# Power_Board_Schematic_Ver_A.net
KiCad netlist of a schematic drawn in Altium Designer
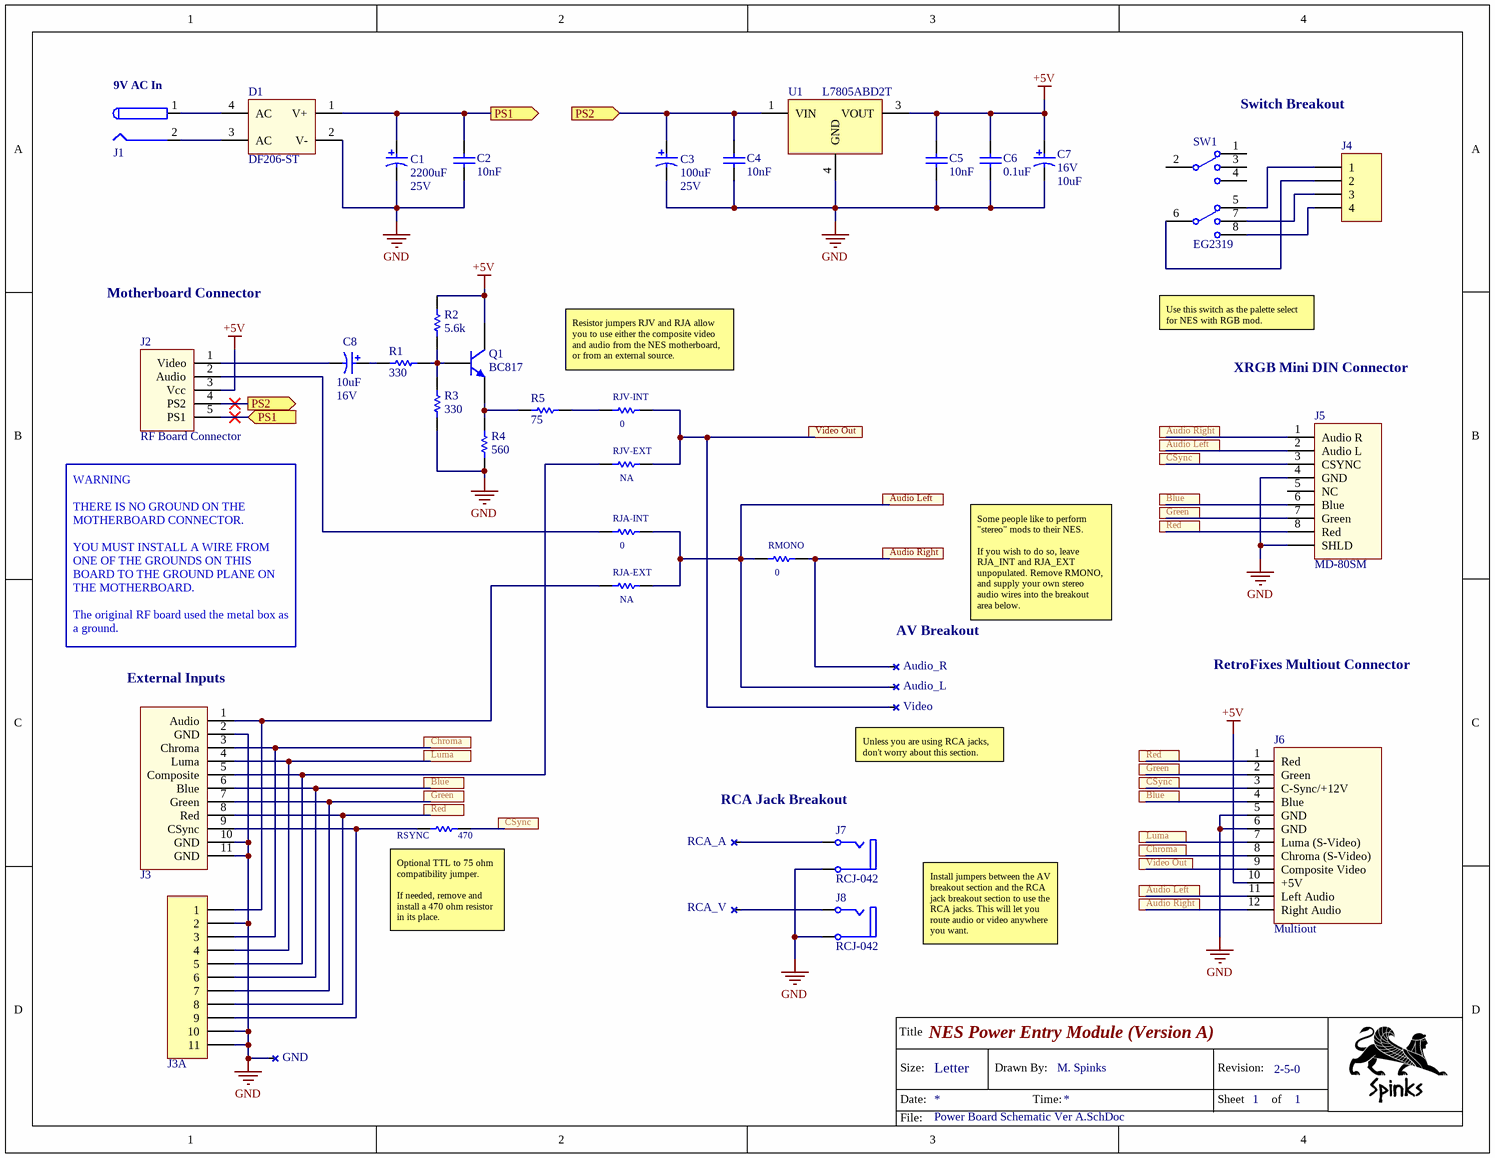
[diagram p0: Power Board Schematic Ver A.SchDoc]

(export (version "E")
  (design (tool "Eeschema 10.0.6"))
  (components
    (comp (ref "Audio_L")
      (value "Wire Pad")
      (footprint "WIREPAD-09-15")
      (description "Wire Pad, 1 Pin, Through Hole, Vertical")
      (libsource (lib "Connectors") (part "-Wire Pad"))
    )
    (comp (ref "Audio_R")
      (value "Wire Pad")
      (footprint "WIREPAD-09-15")
      (description "Wire Pad, 1 Pin, Through Hole, Vertical")
      (libsource (lib "Connectors") (part "-Wire Pad"))
    )
    (comp (ref "C1")
      (value "2200uF")
      (footprint "TH CAP-12.5X25MM-A1K2")
      (description "CAP, ALUM, TH, 12.5x25mm, 2200uF, 25V, 20%, Pitch 5.0mm")
      (fields
        (field (name "VOLTAGE") "25V")
        (field (name "REFERENCEPART") "ECA-1EHG222")
        (field (name "Comment") "Cap Aluminum")
      )
      (libsource (lib "Passive Components") (part "TH-ALUM-8-22-25V (ECA-1EHG222)"))
    )
    (comp (ref "C2")
      (value "10nF")
      (footprint "CAP 0805_N")
      (description "CAP, CER, 0805, 10nF, 50V, X7R, 10%")
      (fields (field (name "VOLTAGE") "50V") (field (name "REFERENCEPART") "VJ0603Y103KXACW1BC"))
      (libsource (lib "Passive Components") (part "0603-X7R-3-10-50V"))
    )
    (comp (ref "C3")
      (value "100uF")
      (footprint "TH CAP-6.3X11MM-A1K2")
      (description "CAP, ALUM, TH, 6.3x11mm, 100uF, 25V, 20%, Pitch 2.5mm")
      (fields
        (field (name "VOLTAGE") "25V")
        (field (name "REFERENCEPART") "ECA-1EM101")
        (field (name "Comment") "Cap Aluminum")
      )
      (libsource (lib "Passive Components") (part "TH-ALUM-7-10-25V (ECA-1EM101)"))
    )
    (comp (ref "C4")
      (value "10nF")
      (footprint "CAP 0805_N")
      (description "CAP, CER, 0805, 10nF, 50V, X7R, 10%")
      (fields (field (name "VOLTAGE") "50V") (field (name "REFERENCEPART") "VJ0603Y103KXACW1BC"))
      (libsource (lib "Passive Components") (part "0603-X7R-3-10-50V"))
    )
    (comp (ref "C5")
      (value "10nF")
      (footprint "CAP 0805_N")
      (description "CAP, CER, 0805, 10nF, 50V, X7R, 10%")
      (fields (field (name "VOLTAGE") "50V") (field (name "REFERENCEPART") "VJ0603Y103KXACW1BC"))
      (libsource (lib "Passive Components") (part "0603-X7R-3-10-50V"))
    )
    (comp (ref "C6")
      (value "0.1uF")
      (footprint "CAP 0805_N")
      (description "CAP, CER, 0805, 0.1uF, 50V, X7R, 10%")
      (fields (field (name "VOLTAGE") "50V") (field (name "REFERENCEPART") "VJ0805Y104KXXCW1BC"))
      (libsource (lib "Passive Components") (part "0805-X7R-4-10-50V"))
    )
    (comp (ref "C7")
      (value "10uF")
      (footprint "CAP EIA-A (3216) A1K2")
      (description "CAP, TANT,  1206, 10uF, 16V, 10%")
      (fields (field (name "VOLTAGE") "16V") (field (name "Comment") "Cap Tantalum"))
      (libsource (lib "Passive Components") (part "1206-TANT-6-10-16V (TAJA106K016RNJ)"))
    )
    (comp (ref "C8")
      (value "10uF")
      (footprint "CAP EIA-A (3216) A1K2")
      (description "CAP, TANT,  1206, 10uF, 16V, 10%")
      (fields (field (name "VOLTAGE") "16V") (field (name "Comment") "Cap Tantalum"))
      (libsource (lib "Passive Components") (part "1206-TANT-6-10-16V (TAJA106K016RNJ)"))
    )
    (comp (ref "D1")
      (value "DF206-ST")
      (footprint "DFS4")
      (description "Full Wave Diode Bridge")
      (libsource (lib "Semiconductors") (part "Bridge (DF206-ST)"))
    )
    (comp (ref "GND")
      (value "Wire Pad")
      (footprint "WIREPAD-09-15")
      (description "Wire Pad, 1 Pin, Through Hole, Vertical")
      (libsource (lib "Connectors") (part "-Wire Pad"))
    )
    (comp (ref "J1")
      (value "PJ-037A")
      (footprint "PWR-JCK-ALT (PJ-037A/B)")
      (description "2.1mm ID, DC Power Supply Connector, 2 Pin")
      (libsource (lib "Connectors") (part "PWR-JCK (PJ-037A)"))
    )
    (comp (ref "J2")
      (value "RF Board Connector")
      (footprint "RF Board Connector")
      (description "Motherboard Connector to RF/Power Module")
      (libsource (lib "Specialty Components") (part "RF Board Connector"))
    )
    (comp (ref "J3")
      (value "1.27mm Pitch")
      (footprint "HDR1x11-15MM VERTL - L")
      (description "Video and audio inputs for the RF Board Mod")
      (libsource (lib "Specialty Components") (part "RF Board Mod Input Header"))
    )
    (comp (ref "J3A")
      (value "1.27mm Pitch")
      (footprint "SMD1x11-127MM")
      (description "Video and audio inputs for the RF Board Mod")
      (libsource (lib "Specialty Components") (part "RF Board Mod Input Header_1"))
    )
    (comp (ref "J4")
      (value "Header 1x4 1.27mm")
      (footprint "HDR1X4-15MM VERT - L")
      (description "Header, 4 Pin, 1.5mm Pitch, Vertical")
      (libsource (lib "Specialty Components") (part "Header 1x4 - 1.5mm Vert"))
    )
    (comp (ref "J5")
      (value "MD-80SM")
      (footprint "MINI-DIN-8-ALT (MD-80SM)")
      (description "8 Pin Mini DIN Connector, Shielded, Through Hole, Right Angle")
      (libsource (lib "Specialty Components") (part "Mini-XRGB (MD-80SM)"))
    )
    (comp (ref "J6")
      (value "Multiout")
      (footprint "Multiout-2")
      (description "SNES Multiout Connector")
      (libsource (lib "Specialty Components") (part "Multiout Connector"))
    )
    (comp (ref "J7")
      (value "RCJ-042")
      (footprint "RCA-JCK-1 (RCJ-042-ALT1)")
      (description "RCA Phono Jack, Right Angle")
      (libsource (lib "Connectors") (part "RCA-JCK-1 (RCJ-042)"))
    )
    (comp (ref "J8")
      (value "RCJ-042")
      (footprint "RCA-JCK-1 (RCJ-042-ALT1)")
      (description "RCA Phono Jack, Right Angle")
      (libsource (lib "Connectors") (part "RCA-JCK-1 (RCJ-042)"))
    )
    (comp (ref "Q1")
      (value "BC817")
      (footprint "SOT23-3")
      (description "General Purpose Transistor, NPN, 3-Pin, B1E2C3")
      (fields (field (name "Comment") "Transistor NPN"))
      (libsource (lib "Semiconductors") (part "BC817 NPN"))
    )
    (comp (ref "R1")
      (value "330")
      (footprint "RES 0805_N")
      (description "RES, SMD")
      (fields (field (name "Comment") "Resistor"))
      (libsource (lib "Passive Components") (part "-Resistor"))
    )
    (comp (ref "R2")
      (value "5.6k")
      (footprint "RES 0805_N")
      (description "RES, SMD")
      (fields (field (name "Comment") "Resistor"))
      (libsource (lib "Passive Components") (part "-Resistor"))
    )
    (comp (ref "R3")
      (value "330")
      (footprint "RES 0805_N")
      (description "RES, SMD")
      (fields (field (name "Comment") "Resistor"))
      (libsource (lib "Passive Components") (part "-Resistor"))
    )
    (comp (ref "R4")
      (value "560")
      (footprint "RES 0805_N")
      (description "RES, SMD")
      (fields (field (name "Comment") "Resistor"))
      (libsource (lib "Passive Components") (part "-Resistor"))
    )
    (comp (ref "R5")
      (value "75")
      (footprint "RES 0805_N")
      (description "RES, SMD")
      (fields (field (name "Comment") "Resistor"))
      (libsource (lib "Passive Components") (part "-Resistor"))
    )
    (comp (ref "RCA_A")
      (value "Wire Pad")
      (footprint "WIREPAD-09-15")
      (description "Wire Pad, 1 Pin, Through Hole, Vertical")
      (libsource (lib "Connectors") (part "-Wire Pad"))
    )
    (comp (ref "RCA_V")
      (value "Wire Pad")
      (footprint "WIREPAD-09-15")
      (description "Wire Pad, 1 Pin, Through Hole, Vertical")
      (libsource (lib "Connectors") (part "-Wire Pad"))
    )
    (comp (ref "RJA-EXT")
      (value "NA")
      (footprint "RES 0805_N")
      (description "RES, SMD")
      (fields (field (name "Comment") "Resistor"))
      (libsource (lib "Passive Components") (part "-Resistor"))
    )
    (comp (ref "RJA-INT")
      (value "0")
      (footprint "RES 0805_N")
      (description "RES, SMD")
      (fields (field (name "Comment") "Resistor"))
      (libsource (lib "Passive Components") (part "-Resistor"))
    )
    (comp (ref "RJV-EXT")
      (value "NA")
      (footprint "RES 0805_N")
      (description "RES, SMD")
      (fields (field (name "Comment") "Resistor"))
      (libsource (lib "Passive Components") (part "-Resistor"))
    )
    (comp (ref "RJV-INT")
      (value "0")
      (footprint "RES 0805_N")
      (description "RES, SMD")
      (fields (field (name "Comment") "Resistor"))
      (libsource (lib "Passive Components") (part "-Resistor"))
    )
    (comp (ref "RMONO")
      (value "0")
      (footprint "RES 0805_N")
      (description "RES, SMD")
      (fields (field (name "Comment") "Resistor"))
      (libsource (lib "Passive Components") (part "-Resistor"))
    )
    (comp (ref "RSYNC")
      (value "470")
      (footprint "RES 0805_N")
      (description "RES, SMD")
      (fields (field (name "Comment") "Resistor"))
      (libsource (lib "Passive Components") (part "-Resistor"))
    )
    (comp (ref "SW1")
      (value "EG2319")
      (footprint "SW-DP3T (EG2319)")
      (description "Dual Pole, Three Throw")
      (fields (field (name "Comment") "DP3T"))
      (libsource (lib "Electromechanical") (part "SW-DP3T (EG2319)"))
    )
    (comp (ref "U1")
      (value "L7805ABD2T")
      (footprint "D2PAK (TO-263)")
      (description "Fixed 5V Regulator, 1.5A, D2PAK")
      (libsource (lib "Integrated Circuits") (part "L7805ABD2T"))
    )
    (comp (ref "Video")
      (value "Wire Pad")
      (footprint "WIREPAD-09-15")
      (description "Wire Pad, 1 Pin, Through Hole, Vertical")
      (libsource (lib "Connectors") (part "-Wire Pad"))
    )
  )
  (nets
    (net (code "1") (name "+5V") (class "Default")
      (node (ref "C5") (pin "2") (pinfunction "2_2") (pintype "passive"))
      (node (ref "C6") (pin "2") (pinfunction "2_2") (pintype "passive"))
      (node (ref "C7") (pin "1") (pinfunction "A_1") (pintype "passive"))
      (node (ref "J2") (pin "3") (pinfunction "Vcc_3") (pintype "passive"))
      (node (ref "J6") (pin "10") (pinfunction "+5V_10") (pintype "passive"))
      (node (ref "Q1") (pin "3") (pinfunction "C_3") (pintype "passive"))
      (node (ref "R2") (pin "1") (pinfunction "1_1") (pintype "passive"))
      (node (ref "U1") (pin "3") (pinfunction "VOUT_3") (pintype "power_in"))
    )
    (net (code "2") (name "/Audio Left") (class "Default")
      (node (ref "Audio_L") (pin "1") (pinfunction "1_1") (pintype "passive"))
      (node (ref "J5") (pin "2") (pinfunction "Audio_L_2") (pintype "passive"))
      (node (ref "J6") (pin "11") (pinfunction "Left_Audio_11") (pintype "passive"))
      (node (ref "RJA-EXT") (pin "1") (pinfunction "1_1") (pintype "passive"))
      (node (ref "RJA-INT") (pin "1") (pinfunction "1_1") (pintype "passive"))
      (node (ref "RMONO") (pin "2") (pinfunction "2_2") (pintype "passive"))
    )
    (net (code "3") (name "/Audio Right") (class "Default")
      (node (ref "Audio_R") (pin "1") (pinfunction "1_1") (pintype "passive"))
      (node (ref "J5") (pin "1") (pinfunction "Audio_R_1") (pintype "passive"))
      (node (ref "J6") (pin "12") (pinfunction "Right_Audio_12") (pintype "passive"))
      (node (ref "RMONO") (pin "1") (pinfunction "1_1") (pintype "passive"))
    )
    (net (code "4") (name "/Blue") (class "Default")
      (node (ref "J3") (pin "6") (pinfunction "Blue_6") (pintype "passive"))
      (node (ref "J3A") (pin "6") (pinfunction "6_6") (pintype "passive"))
      (node (ref "J5") (pin "6") (pinfunction "Blue_6") (pintype "passive"))
      (node (ref "J6") (pin "4") (pinfunction "Blue_4") (pintype "passive"))
    )
    (net (code "5") (name "/CSync") (class "Default")
      (node (ref "J5") (pin "3") (pinfunction "CSYNC_3") (pintype "passive"))
      (node (ref "J6") (pin "3") (pinfunction "C-Sync/+12V_3") (pintype "passive"))
      (node (ref "RSYNC") (pin "1") (pinfunction "1_1") (pintype "passive"))
    )
    (net (code "6") (name "/Chroma") (class "Default")
      (node (ref "J3") (pin "3") (pinfunction "Chroma_3") (pintype "passive"))
      (node (ref "J3A") (pin "3") (pinfunction "3_3") (pintype "passive"))
      (node (ref "J6") (pin "8") (pinfunction "Chroma_(S-Video)_8") (pintype "passive"))
    )
    (net (code "7") (name "/Green") (class "Default")
      (node (ref "J3") (pin "7") (pinfunction "Green_7") (pintype "passive"))
      (node (ref "J3A") (pin "7") (pinfunction "7_7") (pintype "passive"))
      (node (ref "J5") (pin "7") (pinfunction "Green_7") (pintype "passive"))
      (node (ref "J6") (pin "2") (pinfunction "Green_2") (pintype "passive"))
    )
    (net (code "8") (name "/Luma") (class "Default")
      (node (ref "J3") (pin "4") (pinfunction "Luma_4") (pintype "passive"))
      (node (ref "J3A") (pin "4") (pinfunction "4_4") (pintype "passive"))
      (node (ref "J6") (pin "7") (pinfunction "Luma_(S-Video)_7") (pintype "passive"))
    )
    (net (code "9") (name "/PS1") (class "Default")
      (node (ref "C1") (pin "1") (pinfunction "A_1") (pintype "passive"))
      (node (ref "C2") (pin "2") (pinfunction "2_2") (pintype "passive"))
      (node (ref "D1") (pin "1") (pinfunction "V+_1") (pintype "passive"))
      (node (ref "J2") (pin "5") (pinfunction "PS1_5") (pintype "passive"))
    )
    (net (code "10") (name "/PS2") (class "Default")
      (node (ref "C3") (pin "1") (pinfunction "A_1") (pintype "passive"))
      (node (ref "C4") (pin "2") (pinfunction "2_2") (pintype "passive"))
      (node (ref "J2") (pin "4") (pinfunction "PS2_4") (pintype "passive"))
      (node (ref "U1") (pin "1") (pinfunction "VIN_1") (pintype "power_in"))
    )
    (net (code "11") (name "/Red") (class "Default")
      (node (ref "J3") (pin "8") (pinfunction "Red_8") (pintype "passive"))
      (node (ref "J3A") (pin "8") (pinfunction "8_8") (pintype "passive"))
      (node (ref "J5") (pin "8") (pinfunction "Red_8") (pintype "passive"))
      (node (ref "J6") (pin "1") (pinfunction "Red_1") (pintype "passive"))
    )
    (net (code "12") (name "/Video Out") (class "Default")
      (node (ref "J6") (pin "9") (pinfunction "Composite_Video_9") (pintype "passive"))
      (node (ref "RJV-EXT") (pin "1") (pinfunction "1_1") (pintype "passive"))
      (node (ref "RJV-INT") (pin "1") (pinfunction "1_1") (pintype "passive"))
      (node (ref "Video") (pin "1") (pinfunction "1_1") (pintype "passive"))
    )
    (net (code "13") (name "GND") (class "Default")
      (node (ref "C1") (pin "2") (pinfunction "K_2") (pintype "passive"))
      (node (ref "C2") (pin "1") (pinfunction "1_1") (pintype "passive"))
      (node (ref "C3") (pin "2") (pinfunction "K_2") (pintype "passive"))
      (node (ref "C4") (pin "1") (pinfunction "1_1") (pintype "passive"))
      (node (ref "C5") (pin "1") (pinfunction "1_1") (pintype "passive"))
      (node (ref "C6") (pin "1") (pinfunction "1_1") (pintype "passive"))
      (node (ref "C7") (pin "2") (pinfunction "K_2") (pintype "passive"))
      (node (ref "D1") (pin "2") (pinfunction "V-_2") (pintype "passive"))
      (node (ref "GND") (pin "1") (pinfunction "1_1") (pintype "passive"))
      (node (ref "J3") (pin "10") (pinfunction "GND_10") (pintype "passive"))
      (node (ref "J3") (pin "11") (pinfunction "GND_11") (pintype "passive"))
      (node (ref "J3") (pin "2") (pinfunction "GND_2") (pintype "passive"))
      (node (ref "J3A") (pin "10") (pinfunction "10_10") (pintype "passive"))
      (node (ref "J3A") (pin "11") (pinfunction "11_11") (pintype "passive"))
      (node (ref "J3A") (pin "2") (pinfunction "2_2") (pintype "passive"))
      (node (ref "J5") (pin "4") (pinfunction "GND_4") (pintype "passive"))
      (node (ref "J5") (pin "SHLD") (pinfunction "SHLD_SHLD") (pintype "passive"))
      (node (ref "J6") (pin "5") (pinfunction "GND_5") (pintype "passive"))
      (node (ref "J6") (pin "6") (pinfunction "GND_6") (pintype "passive"))
      (node (ref "J7") (pin "2") (pinfunction "Sleeve_2") (pintype "passive"))
      (node (ref "J8") (pin "2") (pinfunction "Sleeve_2") (pintype "passive"))
      (node (ref "R3") (pin "2") (pinfunction "2_2") (pintype "passive"))
      (node (ref "R4") (pin "1") (pinfunction "1_1") (pintype "passive"))
      (node (ref "U1") (pin "4") (pinfunction "GND_4") (pintype "passive"))
    )
    (net (code "14") (name "Net-(C8-A)") (class "Default")
      (node (ref "C8") (pin "1") (pinfunction "A_1") (pintype "passive"))
      (node (ref "R1") (pin "2") (pinfunction "2_2") (pintype "passive"))
    )
    (net (code "15") (name "Net-(C8-K)") (class "Default")
      (node (ref "C8") (pin "2") (pinfunction "K_2") (pintype "passive"))
      (node (ref "J2") (pin "1") (pinfunction "Video_1") (pintype "passive"))
    )
    (net (code "16") (name "Net-(D1-AC-Pad3)") (class "Default")
      (node (ref "D1") (pin "3") (pinfunction "AC_3") (pintype "passive"))
      (node (ref "J1") (pin "2") (pinfunction "2_2") (pintype "power_in"))
    )
    (net (code "17") (name "Net-(D1-AC-Pad4)") (class "Default")
      (node (ref "D1") (pin "4") (pinfunction "AC_4") (pintype "passive"))
      (node (ref "J1") (pin "1") (pinfunction "1_1") (pintype "power_in"))
    )
    (net (code "18") (name "Net-(J2-Audio)") (class "Default")
      (node (ref "J2") (pin "2") (pinfunction "Audio_2") (pintype "passive"))
      (node (ref "RJA-INT") (pin "2") (pinfunction "2_2") (pintype "passive"))
    )
    (net (code "19") (name "Net-(J3-Audio)") (class "Default")
      (node (ref "J3") (pin "1") (pinfunction "Audio_1") (pintype "passive"))
      (node (ref "J3A") (pin "1") (pinfunction "1_1") (pintype "passive"))
      (node (ref "RJA-EXT") (pin "2") (pinfunction "2_2") (pintype "passive"))
    )
    (net (code "20") (name "Net-(J3-CSync)") (class "Default")
      (node (ref "J3") (pin "9") (pinfunction "CSync_9") (pintype "passive"))
      (node (ref "J3A") (pin "9") (pinfunction "9_9") (pintype "passive"))
      (node (ref "RSYNC") (pin "2") (pinfunction "2_2") (pintype "passive"))
    )
    (net (code "21") (name "Net-(J3-Composite)") (class "Default")
      (node (ref "J3") (pin "5") (pinfunction "Composite_5") (pintype "passive"))
      (node (ref "J3A") (pin "5") (pinfunction "5_5") (pintype "passive"))
      (node (ref "RJV-EXT") (pin "2") (pinfunction "2_2") (pintype "passive"))
    )
    (net (code "22") (name "Net-(J4-Pad1)") (class "Default")
      (node (ref "J4") (pin "1") (pinfunction "1_1") (pintype "passive"))
      (node (ref "SW1") (pin "5") (pinfunction "5_5") (pintype "passive"))
    )
    (net (code "23") (name "Net-(J4-Pad2)") (class "Default")
      (node (ref "J4") (pin "2") (pinfunction "2_2") (pintype "passive"))
      (node (ref "SW1") (pin "6") (pinfunction "6_6") (pintype "passive"))
    )
    (net (code "24") (name "Net-(J4-Pad3)") (class "Default")
      (node (ref "J4") (pin "3") (pinfunction "3_3") (pintype "passive"))
      (node (ref "SW1") (pin "7") (pinfunction "7_7") (pintype "passive"))
    )
    (net (code "25") (name "Net-(J4-Pad4)") (class "Default")
      (node (ref "J4") (pin "4") (pinfunction "4_4") (pintype "passive"))
      (node (ref "SW1") (pin "8") (pinfunction "8_8") (pintype "passive"))
    )
    (net (code "26") (name "Net-(J7-Tip)") (class "Default")
      (node (ref "J7") (pin "1") (pinfunction "Tip_1") (pintype "passive"))
      (node (ref "RCA_A") (pin "1") (pinfunction "1_1") (pintype "passive"))
    )
    (net (code "27") (name "Net-(J8-Tip)") (class "Default")
      (node (ref "J8") (pin "1") (pinfunction "Tip_1") (pintype "passive"))
      (node (ref "RCA_V") (pin "1") (pinfunction "1_1") (pintype "passive"))
    )
    (net (code "28") (name "Net-(Q1-B)") (class "Default")
      (node (ref "Q1") (pin "1") (pinfunction "B_1") (pintype "passive"))
      (node (ref "R1") (pin "1") (pinfunction "1_1") (pintype "passive"))
      (node (ref "R2") (pin "2") (pinfunction "2_2") (pintype "passive"))
      (node (ref "R3") (pin "1") (pinfunction "1_1") (pintype "passive"))
    )
    (net (code "29") (name "Net-(Q1-E)") (class "Default")
      (node (ref "Q1") (pin "2") (pinfunction "E_2") (pintype "passive"))
      (node (ref "R4") (pin "2") (pinfunction "2_2") (pintype "passive"))
      (node (ref "R5") (pin "2") (pinfunction "2_2") (pintype "passive"))
    )
    (net (code "30") (name "Net-(R5-Pad1)") (class "Default")
      (node (ref "R5") (pin "1") (pinfunction "1_1") (pintype "passive"))
      (node (ref "RJV-INT") (pin "2") (pinfunction "2_2") (pintype "passive"))
    )
    (net (code "31") (name "unconnected-(J5-NC-Pad5)") (class "Default")
      (node (ref "J5") (pin "5") (pinfunction "NC_5") (pintype "passive"))
    )
    (net (code "32") (name "unconnected-(SW1-Pad1)") (class "Default")
      (node (ref "SW1") (pin "1") (pinfunction "1_1") (pintype "passive"))
    )
    (net (code "33") (name "unconnected-(SW1-Pad2)") (class "Default")
      (node (ref "SW1") (pin "2") (pinfunction "2_2") (pintype "passive"))
    )
    (net (code "34") (name "unconnected-(SW1-Pad3)") (class "Default")
      (node (ref "SW1") (pin "3") (pinfunction "3_3") (pintype "passive"))
    )
    (net (code "35") (name "unconnected-(SW1-Pad4)") (class "Default")
      (node (ref "SW1") (pin "4") (pinfunction "4_4") (pintype "passive"))
    )
  )
)
